# Sat_Cape_v8.net
KiCad netlist of a schematic drawn in EAGLE
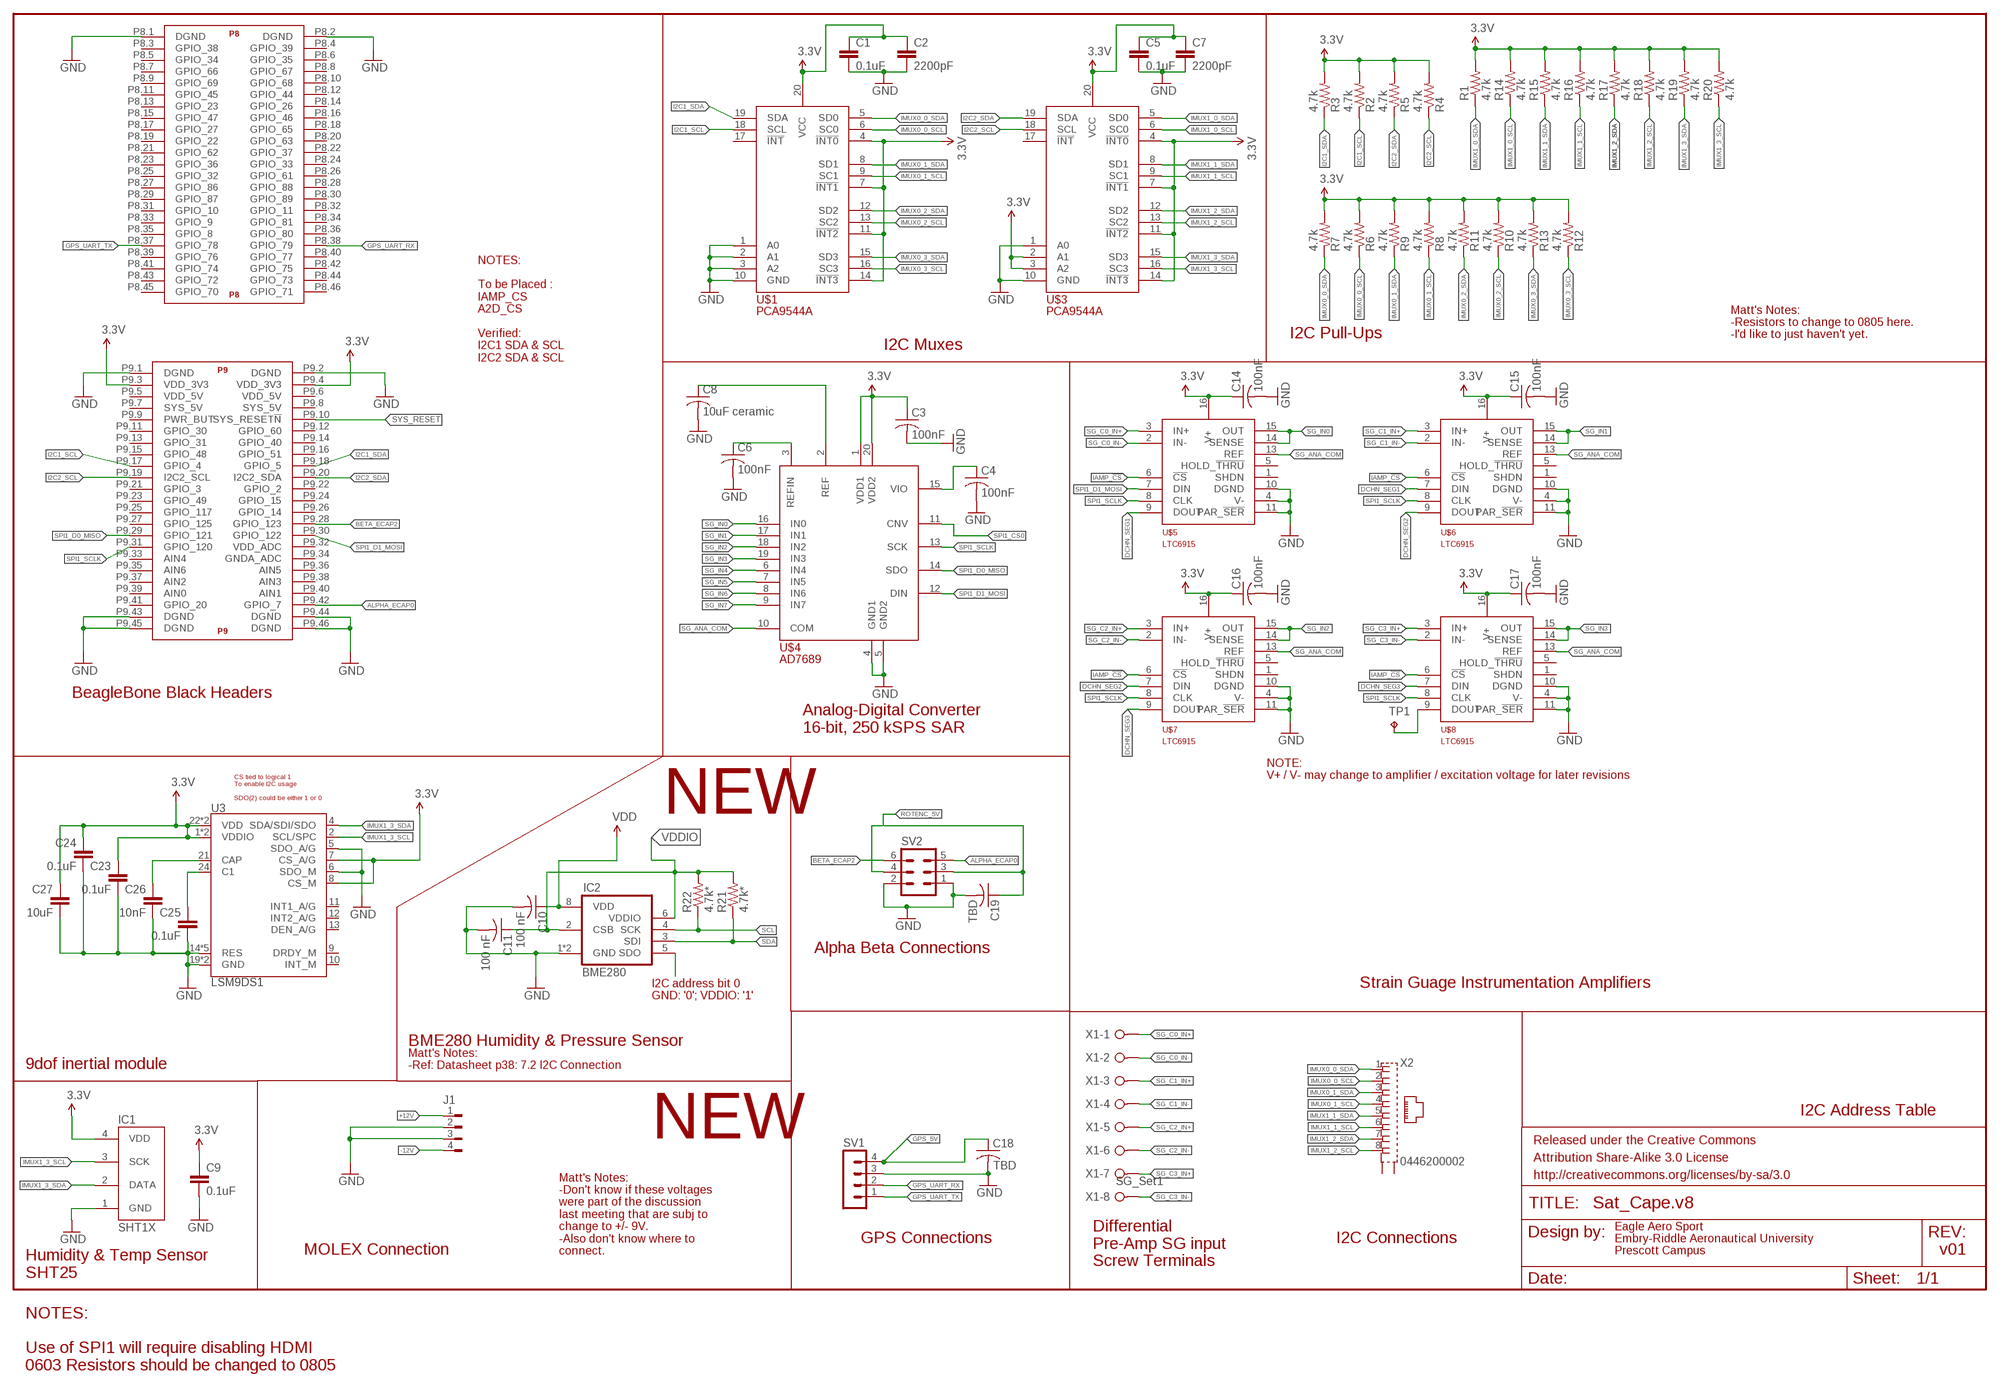
[diagram p0: schematic, sheet 1]

(export (version "E")
  (design (tool "Eeschema 10.0.6"))
  (components
    (comp (ref "C1")
      (value "0.1uF")
      (footprint "eagle-import:0603-CAP")
      (libsource (lib "eagle-import") (part "0.1UF-25V(+80/-20%)(0603)"))
    )
    (comp (ref "C2")
      (value "2200pF")
      (footprint "eagle-import:0603-CAP")
      (libsource (lib "eagle-import") (part "0.1UF-25V(+80/-20%)(0603)"))
    )
    (comp (ref "C3")
      (value "100nF")
      (footprint "eagle-import:C0805")
      (libsource (lib "eagle-import") (part "C-USC0805"))
    )
    (comp (ref "C4")
      (value "100nF")
      (footprint "eagle-import:C0805")
      (libsource (lib "eagle-import") (part "C-USC0805"))
    )
    (comp (ref "C5")
      (value "0.1uF")
      (footprint "eagle-import:0603-CAP")
      (libsource (lib "eagle-import") (part "0.1UF-25V(+80/-20%)(0603)"))
    )
    (comp (ref "C6")
      (value "100nF")
      (footprint "eagle-import:C0805")
      (libsource (lib "eagle-import") (part "C-USC0805"))
    )
    (comp (ref "C7")
      (value "2200pF")
      (footprint "eagle-import:0603-CAP")
      (libsource (lib "eagle-import") (part "0.1UF-25V(+80/-20%)(0603)"))
    )
    (comp (ref "C8")
      (value "10uF ceramic")
      (footprint "eagle-import:C0805")
      (libsource (lib "eagle-import") (part "C-USC0805"))
    )
    (comp (ref "C9")
      (value "0.1uF")
      (footprint "eagle-import:0603-CAP")
      (libsource (lib "eagle-import") (part "0.1UF-25V(+80/-20%)(0603)"))
    )
    (comp (ref "C10")
      (value "100 nF")
      (footprint "eagle-import:C0805")
      (libsource (lib "eagle-import") (part "C-USC0805"))
    )
    (comp (ref "C11")
      (value "100 nF")
      (footprint "eagle-import:C0805")
      (libsource (lib "eagle-import") (part "C-USC0805"))
    )
    (comp (ref "C14")
      (value "100nF")
      (footprint "eagle-import:C0805")
      (libsource (lib "eagle-import") (part "C-USC0805"))
    )
    (comp (ref "C15")
      (value "100nF")
      (footprint "eagle-import:C0805")
      (libsource (lib "eagle-import") (part "C-USC0805"))
    )
    (comp (ref "C16")
      (value "100nF")
      (footprint "eagle-import:C0805")
      (libsource (lib "eagle-import") (part "C-USC0805"))
    )
    (comp (ref "C17")
      (value "100nF")
      (footprint "eagle-import:C0805")
      (libsource (lib "eagle-import") (part "C-USC0805"))
    )
    (comp (ref "C18")
      (value "TBD")
      (footprint "eagle-import:C0805")
      (libsource (lib "eagle-import") (part "C-USC0805"))
    )
    (comp (ref "C19")
      (value "TBD")
      (footprint "eagle-import:C0805")
      (libsource (lib "eagle-import") (part "C-USC0805"))
    )
    (comp (ref "C23")
      (value "0.1uF")
      (footprint "eagle-import:0603-CAP")
      (libsource (lib "eagle-import") (part "0.1UF-25V(+80/-20%)(0603)"))
    )
    (comp (ref "C24")
      (value "0.1uF")
      (footprint "eagle-import:0603-CAP")
      (libsource (lib "eagle-import") (part "0.1UF-25V(+80/-20%)(0603)"))
    )
    (comp (ref "C25")
      (value "0.1uF")
      (footprint "eagle-import:0603-CAP")
      (libsource (lib "eagle-import") (part "0.1UF-25V(+80/-20%)(0603)"))
    )
    (comp (ref "C26")
      (value "10nF")
      (footprint "eagle-import:0603-CAP")
      (libsource (lib "eagle-import") (part "10NF/10000PF-50V-10%(0603)"))
    )
    (comp (ref "C27")
      (value "10uF")
      (footprint "eagle-import:0603-CAP")
      (libsource (lib "eagle-import") (part "10UF-6.3V-20%(0603)"))
    )
    (comp (ref "FRAME1")
      (value "FRAME-LEDGER")
      (footprint "eagle-import:CREATIVE_COMMONS")
      (libsource (lib "eagle-import") (part "FRAME-LEDGER"))
    )
    (comp (ref "IC1")
      (value "SHT1X")
      (footprint "eagle-import:SHT1X")
      (libsource (lib "eagle-import") (part "SHT1X"))
    )
    (comp (ref "IC2")
      (value "BME280")
      (footprint "eagle-import:BME280")
      (libsource (lib "eagle-import") (part "BME280"))
    )
    (comp (ref "J1")
      (value "FLOPPY-4350211")
      (footprint "eagle-import:350211")
      (libsource (lib "eagle-import") (part "FLOPPY-4350211"))
    )
    (comp (ref "R1")
      (value "4.7k")
      (footprint "eagle-import:R0805")
      (libsource (lib "eagle-import") (part "resistor_R-US_R0805"))
    )
    (comp (ref "R2")
      (value "4.7k")
      (footprint "eagle-import:0603-RES")
      (libsource (lib "eagle-import") (part "10KOHM1/10W1%(0603)0603"))
    )
    (comp (ref "R3")
      (value "4.7k")
      (footprint "eagle-import:0603-RES")
      (libsource (lib "eagle-import") (part "10KOHM1/10W1%(0603)0603"))
    )
    (comp (ref "R4")
      (value "4.7k")
      (footprint "eagle-import:0603-RES")
      (libsource (lib "eagle-import") (part "10KOHM1/10W1%(0603)0603"))
    )
    (comp (ref "R5")
      (value "4.7k")
      (footprint "eagle-import:0603-RES")
      (libsource (lib "eagle-import") (part "10KOHM1/10W1%(0603)0603"))
    )
    (comp (ref "R6")
      (value "4.7k")
      (footprint "eagle-import:0603-RES")
      (libsource (lib "eagle-import") (part "10KOHM1/10W1%(0603)0603"))
    )
    (comp (ref "R7")
      (value "4.7k")
      (footprint "eagle-import:0603-RES")
      (libsource (lib "eagle-import") (part "10KOHM1/10W1%(0603)0603"))
    )
    (comp (ref "R8")
      (value "4.7k")
      (footprint "eagle-import:0603-RES")
      (libsource (lib "eagle-import") (part "10KOHM1/10W1%(0603)0603"))
    )
    (comp (ref "R9")
      (value "4.7k")
      (footprint "eagle-import:0603-RES")
      (libsource (lib "eagle-import") (part "10KOHM1/10W1%(0603)0603"))
    )
    (comp (ref "R10")
      (value "4.7k")
      (footprint "eagle-import:0603-RES")
      (libsource (lib "eagle-import") (part "10KOHM1/10W1%(0603)0603"))
    )
    (comp (ref "R11")
      (value "4.7k")
      (footprint "eagle-import:0603-RES")
      (libsource (lib "eagle-import") (part "10KOHM1/10W1%(0603)0603"))
    )
    (comp (ref "R12")
      (value "4.7k")
      (footprint "eagle-import:0603-RES")
      (libsource (lib "eagle-import") (part "10KOHM1/10W1%(0603)0603"))
    )
    (comp (ref "R13")
      (value "4.7k")
      (footprint "eagle-import:0603-RES")
      (libsource (lib "eagle-import") (part "10KOHM1/10W1%(0603)0603"))
    )
    (comp (ref "R14")
      (value "4.7k")
      (footprint "eagle-import:R0805")
      (libsource (lib "eagle-import") (part "resistor_R-US_R0805"))
    )
    (comp (ref "R15")
      (value "4.7k")
      (footprint "eagle-import:R0805")
      (libsource (lib "eagle-import") (part "resistor_R-US_R0805"))
    )
    (comp (ref "R16")
      (value "4.7k")
      (footprint "eagle-import:R0805")
      (libsource (lib "eagle-import") (part "resistor_R-US_R0805"))
    )
    (comp (ref "R17")
      (value "4.7k")
      (footprint "eagle-import:R0805")
      (libsource (lib "eagle-import") (part "resistor_R-US_R0805"))
    )
    (comp (ref "R18")
      (value "4.7k")
      (footprint "eagle-import:R0805")
      (libsource (lib "eagle-import") (part "resistor_R-US_R0805"))
    )
    (comp (ref "R19")
      (value "4.7k")
      (footprint "eagle-import:R0805")
      (libsource (lib "eagle-import") (part "resistor_R-US_R0805"))
    )
    (comp (ref "R20")
      (value "4.7k")
      (footprint "eagle-import:R0805")
      (libsource (lib "eagle-import") (part "resistor_R-US_R0805"))
    )
    (comp (ref "R21")
      (value "4.7k*")
      (footprint "eagle-import:R0805")
      (libsource (lib "eagle-import") (part "R-US_R0805"))
    )
    (comp (ref "R22")
      (value "4.7k*")
      (footprint "eagle-import:R0805")
      (libsource (lib "eagle-import") (part "R-US_R0805"))
    )
    (comp (ref "SV1")
      (value "MA04-1")
      (footprint "eagle-import:MA04-1")
      (libsource (lib "eagle-import") (part "MA04-1"))
    )
    (comp (ref "SV2")
      (value "MA03-2")
      (footprint "eagle-import:MA03-2")
      (libsource (lib "eagle-import") (part "MA03-2"))
    )
    (comp (ref "TP1")
      (value "TPTP08R")
      (footprint "eagle-import:TP08R")
      (libsource (lib "eagle-import") (part "TPTP08R"))
    )
    (comp (ref "U$1")
      (value "PCA9544A")
      (footprint "eagle-import:TSSOP20")
      (libsource (lib "eagle-import") (part "PCA9544A"))
    )
    (comp (ref "U$2")
      (value "BEAGLE_BONE_BLACK_CAPE")
      (footprint "eagle-import:BEAGLE_BONE_BLACK_CAPE")
      (libsource (lib "eagle-import") (part "BEAGLE_BONE_BLACK_CAPE"))
    )
    (comp (ref "U$3")
      (value "PCA9544A")
      (footprint "eagle-import:TSSOP20")
      (libsource (lib "eagle-import") (part "PCA9544A"))
    )
    (comp (ref "U$4")
      (value "AD7689")
      (footprint "eagle-import:QFN20")
      (libsource (lib "eagle-import") (part "AD7689"))
    )
    (comp (ref "U$5")
      (value "LTC6915")
      (footprint "eagle-import:SSOP16")
      (libsource (lib "eagle-import") (part "LTC6915"))
    )
    (comp (ref "U$6")
      (value "LTC6915")
      (footprint "eagle-import:SSOP16")
      (libsource (lib "eagle-import") (part "LTC6915"))
    )
    (comp (ref "U$7")
      (value "LTC6915")
      (footprint "eagle-import:SSOP16")
      (libsource (lib "eagle-import") (part "LTC6915"))
    )
    (comp (ref "U$8")
      (value "LTC6915")
      (footprint "eagle-import:SSOP16")
      (libsource (lib "eagle-import") (part "LTC6915"))
    )
    (comp (ref "U3")
      (value "LSM9DS1")
      (footprint "eagle-import:LGA24-8X4")
      (libsource (lib "eagle-import") (part "LSM9DS1"))
    )
    (comp (ref "X1")
      (value "SG_Set1")
      (footprint "eagle-import:W237-8P")
      (libsource (lib "eagle-import") (part "W237-08P"))
    )
    (comp (ref "X2")
      (value "0446200002")
      (footprint "eagle-import:0446200002")
      (fields (field (name "MF") "MOLEX"))
      (libsource (lib "eagle-import") (part "0446200002"))
    )
  )
  (nets
    (net (code "1") (name "+12V") (class "Default")
      (node (ref "J1") (pin "1") (pinfunction "1_1") (pintype "passive"))
    )
    (net (code "2") (name "-12V") (class "Default")
      (node (ref "J1") (pin "4") (pinfunction "4_4") (pintype "passive"))
    )
    (net (code "3") (name "/IAMP_~{CS}") (class "Default")
      (node (ref "U$5") (pin "6") (pinfunction "~{CS}_6") (pintype "bidirectional"))
      (node (ref "U$6") (pin "6") (pinfunction "~{CS}_6") (pintype "bidirectional"))
      (node (ref "U$7") (pin "6") (pinfunction "~{CS}_6") (pintype "bidirectional"))
      (node (ref "U$8") (pin "6") (pinfunction "~{CS}_6") (pintype "bidirectional"))
    )
    (net (code "4") (name "3.3V") (class "Default")
      (node (ref "C1") (pin "1") (pinfunction "1_1") (pintype "passive"))
      (node (ref "C14") (pin "1") (pinfunction "1_1") (pintype "passive"))
      (node (ref "C15") (pin "1") (pinfunction "1_1") (pintype "passive"))
      (node (ref "C16") (pin "1") (pinfunction "1_1") (pintype "passive"))
      (node (ref "C17") (pin "1") (pinfunction "1_1") (pintype "passive"))
      (node (ref "C2") (pin "1") (pinfunction "1_1") (pintype "passive"))
      (node (ref "C23") (pin "1") (pinfunction "1_1") (pintype "passive"))
      (node (ref "C24") (pin "1") (pinfunction "1_1") (pintype "passive"))
      (node (ref "C27") (pin "1") (pinfunction "1_1") (pintype "passive"))
      (node (ref "C3") (pin "1") (pinfunction "1_1") (pintype "passive"))
      (node (ref "C5") (pin "1") (pinfunction "1_1") (pintype "passive"))
      (node (ref "C7") (pin "1") (pinfunction "1_1") (pintype "passive"))
      (node (ref "C9") (pin "1") (pinfunction "1_1") (pintype "passive"))
      (node (ref "IC1") (pin "4") (pinfunction "VDD_4") (pintype "power_in"))
      (node (ref "R1") (pin "2") (pinfunction "2_2") (pintype "passive"))
      (node (ref "R10") (pin "2") (pinfunction "2_2") (pintype "passive"))
      (node (ref "R11") (pin "2") (pinfunction "2_2") (pintype "passive"))
      (node (ref "R12") (pin "2") (pinfunction "2_2") (pintype "passive"))
      (node (ref "R13") (pin "2") (pinfunction "2_2") (pintype "passive"))
      (node (ref "R14") (pin "2") (pinfunction "2_2") (pintype "passive"))
      (node (ref "R15") (pin "2") (pinfunction "2_2") (pintype "passive"))
      (node (ref "R16") (pin "2") (pinfunction "2_2") (pintype "passive"))
      (node (ref "R17") (pin "2") (pinfunction "2_2") (pintype "passive"))
      (node (ref "R18") (pin "2") (pinfunction "2_2") (pintype "passive"))
      (node (ref "R19") (pin "2") (pinfunction "2_2") (pintype "passive"))
      (node (ref "R2") (pin "2") (pinfunction "2_2") (pintype "passive"))
      (node (ref "R20") (pin "2") (pinfunction "2_2") (pintype "passive"))
      (node (ref "R3") (pin "2") (pinfunction "2_2") (pintype "passive"))
      (node (ref "R4") (pin "2") (pinfunction "2_2") (pintype "passive"))
      (node (ref "R5") (pin "2") (pinfunction "2_2") (pintype "passive"))
      (node (ref "R6") (pin "2") (pinfunction "2_2") (pintype "passive"))
      (node (ref "R7") (pin "2") (pinfunction "2_2") (pintype "passive"))
      (node (ref "R8") (pin "2") (pinfunction "2_2") (pintype "passive"))
      (node (ref "R9") (pin "2") (pinfunction "2_2") (pintype "passive"))
      (node (ref "U$1") (pin "11") (pinfunction "~{INT2}_11") (pintype "input"))
      (node (ref "U$1") (pin "14") (pinfunction "~{INT3}_14") (pintype "input"))
      (node (ref "U$1") (pin "20") (pinfunction "VCC_20") (pintype "power_in"))
      (node (ref "U$1") (pin "4") (pinfunction "~{INT0}_4") (pintype "input"))
      (node (ref "U$1") (pin "7") (pinfunction "~{INT1}_7") (pintype "input"))
      (node (ref "U$2") (pin "P9.3") (pinfunction "VDD_3V3_P9.3") (pintype "bidirectional"))
      (node (ref "U$2") (pin "P9.4") (pinfunction "VDD_3V3_P9.4") (pintype "bidirectional"))
      (node (ref "U$3") (pin "11") (pinfunction "~{INT2}_11") (pintype "input"))
      (node (ref "U$3") (pin "14") (pinfunction "~{INT3}_14") (pintype "input"))
      (node (ref "U$3") (pin "2") (pinfunction "A1_2") (pintype "input"))
      (node (ref "U$3") (pin "20") (pinfunction "VCC_20") (pintype "power_in"))
      (node (ref "U$3") (pin "3") (pinfunction "A2_3") (pintype "input"))
      (node (ref "U$3") (pin "4") (pinfunction "~{INT0}_4") (pintype "input"))
      (node (ref "U$3") (pin "7") (pinfunction "~{INT1}_7") (pintype "input"))
      (node (ref "U$4") (pin "1") (pinfunction "VDD1_1") (pintype "bidirectional"))
      (node (ref "U$4") (pin "20") (pinfunction "VDD2_20") (pintype "bidirectional"))
      (node (ref "U$5") (pin "16") (pinfunction "V+_16") (pintype "bidirectional"))
      (node (ref "U$6") (pin "16") (pinfunction "V+_16") (pintype "bidirectional"))
      (node (ref "U$7") (pin "16") (pinfunction "V+_16") (pintype "bidirectional"))
      (node (ref "U$8") (pin "16") (pinfunction "V+_16") (pintype "bidirectional"))
      (node (ref "U3") (pin "1") (pinfunction "VDDIO_1") (pintype "bidirectional"))
      (node (ref "U3") (pin "22") (pinfunction "VDD_22") (pintype "bidirectional"))
      (node (ref "U3") (pin "23") (pinfunction "VDD_23") (pintype "bidirectional"))
      (node (ref "U3") (pin "3") (pinfunction "VDDIO_3") (pintype "bidirectional"))
      (node (ref "U3") (pin "7") (pinfunction "CS_A/G_7") (pintype "bidirectional"))
      (node (ref "U3") (pin "8") (pinfunction "CS_M_8") (pintype "bidirectional"))
    )
    (net (code "5") (name "ALPHA_ECAP0") (class "Default")
      (node (ref "SV2") (pin "5") (pinfunction "5_5") (pintype "passive"))
      (node (ref "U$2") (pin "P9.42") (pinfunction "GPIO_7_P9.42") (pintype "bidirectional"))
    )
    (net (code "6") (name "BETA_ECAP2") (class "Default")
      (node (ref "SV2") (pin "6") (pinfunction "6_6") (pintype "passive"))
      (node (ref "U$2") (pin "P9.28") (pinfunction "GPIO_123_P9.28") (pintype "bidirectional"))
    )
    (net (code "7") (name "DCHN_SEG1") (class "Default")
      (node (ref "U$5") (pin "9") (pinfunction "DOUT_9") (pintype "bidirectional"))
      (node (ref "U$6") (pin "7") (pinfunction "DIN_7") (pintype "bidirectional"))
    )
    (net (code "8") (name "DCHN_SEG2") (class "Default")
      (node (ref "U$6") (pin "9") (pinfunction "DOUT_9") (pintype "bidirectional"))
      (node (ref "U$7") (pin "7") (pinfunction "DIN_7") (pintype "bidirectional"))
    )
    (net (code "9") (name "DCHN_SEG3") (class "Default")
      (node (ref "U$7") (pin "9") (pinfunction "DOUT_9") (pintype "bidirectional"))
      (node (ref "U$8") (pin "7") (pinfunction "DIN_7") (pintype "bidirectional"))
    )
    (net (code "10") (name "GND") (class "Default")
      (node (ref "C1") (pin "2") (pinfunction "2_2") (pintype "passive"))
      (node (ref "C10") (pin "2") (pinfunction "2_2") (pintype "passive"))
      (node (ref "C11") (pin "2") (pinfunction "2_2") (pintype "passive"))
      (node (ref "C14") (pin "2") (pinfunction "2_2") (pintype "passive"))
      (node (ref "C15") (pin "2") (pinfunction "2_2") (pintype "passive"))
      (node (ref "C16") (pin "2") (pinfunction "2_2") (pintype "passive"))
      (node (ref "C17") (pin "2") (pinfunction "2_2") (pintype "passive"))
      (node (ref "C18") (pin "2") (pinfunction "2_2") (pintype "passive"))
      (node (ref "C19") (pin "2") (pinfunction "2_2") (pintype "passive"))
      (node (ref "C2") (pin "2") (pinfunction "2_2") (pintype "passive"))
      (node (ref "C23") (pin "2") (pinfunction "2_2") (pintype "passive"))
      (node (ref "C24") (pin "2") (pinfunction "2_2") (pintype "passive"))
      (node (ref "C25") (pin "2") (pinfunction "2_2") (pintype "passive"))
      (node (ref "C26") (pin "2") (pinfunction "2_2") (pintype "passive"))
      (node (ref "C27") (pin "2") (pinfunction "2_2") (pintype "passive"))
      (node (ref "C3") (pin "2") (pinfunction "2_2") (pintype "passive"))
      (node (ref "C4") (pin "2") (pinfunction "2_2") (pintype "passive"))
      (node (ref "C5") (pin "2") (pinfunction "2_2") (pintype "passive"))
      (node (ref "C6") (pin "2") (pinfunction "2_2") (pintype "passive"))
      (node (ref "C7") (pin "2") (pinfunction "2_2") (pintype "passive"))
      (node (ref "C8") (pin "2") (pinfunction "2_2") (pintype "passive"))
      (node (ref "C9") (pin "2") (pinfunction "2_2") (pintype "passive"))
      (node (ref "IC1") (pin "1") (pinfunction "GND_1") (pintype "power_in"))
      (node (ref "IC2") (pin "1") (pinfunction "GND_1") (pintype "power_in"))
      (node (ref "IC2") (pin "7") (pinfunction "GND_7") (pintype "power_in"))
      (node (ref "J1") (pin "2") (pinfunction "2_2") (pintype "passive"))
      (node (ref "J1") (pin "3") (pinfunction "3_3") (pintype "passive"))
      (node (ref "SV1") (pin "3") (pinfunction "3_3") (pintype "passive"))
      (node (ref "SV2") (pin "1") (pinfunction "1_1") (pintype "passive"))
      (node (ref "SV2") (pin "2") (pinfunction "2_2") (pintype "passive"))
      (node (ref "U$1") (pin "1") (pinfunction "A0_1") (pintype "input"))
      (node (ref "U$1") (pin "10") (pinfunction "GND_10") (pintype "power_in"))
      (node (ref "U$1") (pin "2") (pinfunction "A1_2") (pintype "input"))
      (node (ref "U$1") (pin "3") (pinfunction "A2_3") (pintype "input"))
      (node (ref "U$2") (pin "P8.1") (pinfunction "DGND_P8.1") (pintype "bidirectional"))
      (node (ref "U$2") (pin "P8.2") (pinfunction "DGND_P8.2") (pintype "bidirectional"))
      (node (ref "U$2") (pin "P9.1") (pinfunction "DGND_P9.1") (pintype "bidirectional"))
      (node (ref "U$2") (pin "P9.2") (pinfunction "DGND_P9.2") (pintype "bidirectional"))
      (node (ref "U$2") (pin "P9.43") (pinfunction "DGND_P9.43") (pintype "bidirectional"))
      (node (ref "U$2") (pin "P9.44") (pinfunction "DGND_P9.44") (pintype "bidirectional"))
      (node (ref "U$2") (pin "P9.45") (pinfunction "DGND_P9.45") (pintype "bidirectional"))
      (node (ref "U$2") (pin "P9.46") (pinfunction "DGND_P9.46") (pintype "bidirectional"))
      (node (ref "U$3") (pin "1") (pinfunction "A0_1") (pintype "input"))
      (node (ref "U$3") (pin "10") (pinfunction "GND_10") (pintype "power_in"))
      (node (ref "U$4") (pin "4") (pinfunction "GND1_4") (pintype "bidirectional"))
      (node (ref "U$4") (pin "5") (pinfunction "GND2_5") (pintype "bidirectional"))
      (node (ref "U$5") (pin "10") (pinfunction "DGND_10") (pintype "bidirectional"))
      (node (ref "U$5") (pin "11") (pinfunction "PAR_~{SER}_11") (pintype "bidirectional"))
      (node (ref "U$5") (pin "4") (pinfunction "V-_4") (pintype "bidirectional"))
      (node (ref "U$6") (pin "10") (pinfunction "DGND_10") (pintype "bidirectional"))
      (node (ref "U$6") (pin "11") (pinfunction "PAR_~{SER}_11") (pintype "bidirectional"))
      (node (ref "U$6") (pin "4") (pinfunction "V-_4") (pintype "bidirectional"))
      (node (ref "U$7") (pin "10") (pinfunction "DGND_10") (pintype "bidirectional"))
      (node (ref "U$7") (pin "11") (pinfunction "PAR_~{SER}_11") (pintype "bidirectional"))
      (node (ref "U$7") (pin "4") (pinfunction "V-_4") (pintype "bidirectional"))
      (node (ref "U$8") (pin "10") (pinfunction "DGND_10") (pintype "bidirectional"))
      (node (ref "U$8") (pin "11") (pinfunction "PAR_~{SER}_11") (pintype "bidirectional"))
      (node (ref "U$8") (pin "4") (pinfunction "V-_4") (pintype "bidirectional"))
      (node (ref "U3") (pin "14") (pinfunction "RES_14") (pintype "bidirectional"))
      (node (ref "U3") (pin "15") (pinfunction "RES_15") (pintype "bidirectional"))
      (node (ref "U3") (pin "16") (pinfunction "RES_16") (pintype "bidirectional"))
      (node (ref "U3") (pin "17") (pinfunction "RES_17") (pintype "bidirectional"))
      (node (ref "U3") (pin "18") (pinfunction "RES_18") (pintype "bidirectional"))
      (node (ref "U3") (pin "19") (pinfunction "GND_19") (pintype "bidirectional"))
      (node (ref "U3") (pin "20") (pinfunction "GND_20") (pintype "bidirectional"))
      (node (ref "U3") (pin "5") (pinfunction "SDO_A/G_5") (pintype "bidirectional"))
      (node (ref "U3") (pin "6") (pinfunction "SDO_M_6") (pintype "bidirectional"))
    )
    (net (code "11") (name "GPS_5V") (class "Default")
      (node (ref "C18") (pin "1") (pinfunction "1_1") (pintype "passive"))
      (node (ref "SV1") (pin "4") (pinfunction "4_4") (pintype "passive"))
    )
    (net (code "12") (name "GPS_UART_RX") (class "Default")
      (node (ref "SV1") (pin "2") (pinfunction "2_2") (pintype "passive"))
      (node (ref "U$2") (pin "P8.38") (pinfunction "GPIO_79_P8.38") (pintype "bidirectional"))
    )
    (net (code "13") (name "GPS_UART_TX") (class "Default")
      (node (ref "SV1") (pin "1") (pinfunction "1_1") (pintype "passive"))
      (node (ref "U$2") (pin "P8.37") (pinfunction "GPIO_78_P8.37") (pintype "bidirectional"))
    )
    (net (code "14") (name "I2C1_SCL") (class "Default")
      (node (ref "R2") (pin "1") (pinfunction "1_1") (pintype "passive"))
      (node (ref "U$1") (pin "18") (pinfunction "SCL_18") (pintype "input"))
      (node (ref "U$2") (pin "P9.17") (pinfunction "GPIO_4_P9.17") (pintype "bidirectional"))
    )
    (net (code "15") (name "I2C1_SDA") (class "Default")
      (node (ref "R3") (pin "1") (pinfunction "1_1") (pintype "passive"))
      (node (ref "U$1") (pin "19") (pinfunction "SDA_19") (pintype "bidirectional"))
      (node (ref "U$2") (pin "P9.18") (pinfunction "GPIO_5_P9.18") (pintype "bidirectional"))
    )
    (net (code "16") (name "I2C2_SCL") (class "Default")
      (node (ref "R4") (pin "1") (pinfunction "1_1") (pintype "passive"))
      (node (ref "U$2") (pin "P9.19") (pinfunction "I2C2_SCL_P9.19") (pintype "bidirectional"))
      (node (ref "U$3") (pin "18") (pinfunction "SCL_18") (pintype "input"))
    )
    (net (code "17") (name "I2C2_SDA") (class "Default")
      (node (ref "R5") (pin "1") (pinfunction "1_1") (pintype "passive"))
      (node (ref "U$2") (pin "P9.20") (pinfunction "I2C2_SDA_P9.20") (pintype "bidirectional"))
      (node (ref "U$3") (pin "19") (pinfunction "SDA_19") (pintype "bidirectional"))
    )
    (net (code "18") (name "IMUX0_0_SCL") (class "Default")
      (node (ref "R6") (pin "1") (pinfunction "1_1") (pintype "passive"))
      (node (ref "U$1") (pin "6") (pinfunction "SC0_6") (pintype "output"))
      (node (ref "X2") (pin "2") (pinfunction "2_2") (pintype "passive"))
    )
    (net (code "19") (name "IMUX0_0_SDA") (class "Default")
      (node (ref "R7") (pin "1") (pinfunction "1_1") (pintype "passive"))
      (node (ref "U$1") (pin "5") (pinfunction "SD0_5") (pintype "bidirectional"))
      (node (ref "X2") (pin "1") (pinfunction "1_1") (pintype "passive"))
    )
    (net (code "20") (name "IMUX0_1_SCL") (class "Default")
      (node (ref "R8") (pin "1") (pinfunction "1_1") (pintype "passive"))
      (node (ref "U$1") (pin "9") (pinfunction "SC1_9") (pintype "output"))
      (node (ref "X2") (pin "4") (pinfunction "4_4") (pintype "passive"))
    )
    (net (code "21") (name "IMUX0_1_SDA") (class "Default")
      (node (ref "R9") (pin "1") (pinfunction "1_1") (pintype "passive"))
      (node (ref "U$1") (pin "8") (pinfunction "SD1_8") (pintype "bidirectional"))
      (node (ref "X2") (pin "3") (pinfunction "3_3") (pintype "passive"))
    )
    (net (code "22") (name "IMUX0_2_SCL") (class "Default")
      (node (ref "R10") (pin "1") (pinfunction "1_1") (pintype "passive"))
      (node (ref "U$1") (pin "13") (pinfunction "SC2_13") (pintype "output"))
    )
    (net (code "23") (name "IMUX0_2_SDA") (class "Default")
      (node (ref "R11") (pin "1") (pinfunction "1_1") (pintype "passive"))
      (node (ref "U$1") (pin "12") (pinfunction "SD2_12") (pintype "bidirectional"))
    )
    (net (code "24") (name "IMUX0_3_SCL") (class "Default")
      (node (ref "R12") (pin "1") (pinfunction "1_1") (pintype "passive"))
      (node (ref "U$1") (pin "16") (pinfunction "SC3_16") (pintype "output"))
    )
    (net (code "25") (name "IMUX0_3_SDA") (class "Default")
      (node (ref "R13") (pin "1") (pinfunction "1_1") (pintype "passive"))
      (node (ref "U$1") (pin "15") (pinfunction "SD3_15") (pintype "bidirectional"))
    )
    (net (code "26") (name "IMUX1_0_SCL") (class "Default")
      (node (ref "R14") (pin "1") (pinfunction "1_1") (pintype "passive"))
      (node (ref "U$3") (pin "6") (pinfunction "SC0_6") (pintype "output"))
    )
    (net (code "27") (name "IMUX1_0_SDA") (class "Default")
      (node (ref "R1") (pin "1") (pinfunction "1_1") (pintype "passive"))
      (node (ref "U$3") (pin "5") (pinfunction "SD0_5") (pintype "bidirectional"))
    )
    (net (code "28") (name "IMUX1_1_SCL") (class "Default")
      (node (ref "R16") (pin "1") (pinfunction "1_1") (pintype "passive"))
      (node (ref "U$3") (pin "9") (pinfunction "SC1_9") (pintype "output"))
      (node (ref "X2") (pin "6") (pinfunction "6_6") (pintype "passive"))
    )
    (net (code "29") (name "IMUX1_1_SDA") (class "Default")
      (node (ref "R15") (pin "1") (pinfunction "1_1") (pintype "passive"))
      (node (ref "U$3") (pin "8") (pinfunction "SD1_8") (pintype "bidirectional"))
      (node (ref "X2") (pin "5") (pinfunction "5_5") (pintype "passive"))
    )
    (net (code "30") (name "IMUX1_2_SCL") (class "Default")
      (node (ref "R18") (pin "1") (pinfunction "1_1") (pintype "passive"))
      (node (ref "U$3") (pin "13") (pinfunction "SC2_13") (pintype "output"))
      (node (ref "X2") (pin "8") (pinfunction "8_8") (pintype "passive"))
    )
    (net (code "31") (name "IMUX1_2_SDA") (class "Default")
      (node (ref "R17") (pin "1") (pinfunction "1_1") (pintype "passive"))
      (node (ref "U$3") (pin "12") (pinfunction "SD2_12") (pintype "bidirectional"))
      (node (ref "X2") (pin "7") (pinfunction "7_7") (pintype "passive"))
    )
    (net (code "32") (name "IMUX1_3_SCL") (class "Default")
      (node (ref "IC1") (pin "3") (pinfunction "SCK_3") (pintype "input"))
      (node (ref "R20") (pin "1") (pinfunction "1_1") (pintype "passive"))
      (node (ref "U$3") (pin "16") (pinfunction "SC3_16") (pintype "output"))
      (node (ref "U3") (pin "2") (pinfunction "SCL/SPC_2") (pintype "bidirectional"))
    )
    (net (code "33") (name "IMUX1_3_SDA") (class "Default")
      (node (ref "IC1") (pin "2") (pinfunction "DATA_2") (pintype "open_collector"))
      (node (ref "R19") (pin "1") (pinfunction "1_1") (pintype "passive"))
      (node (ref "U$3") (pin "15") (pinfunction "SD3_15") (pintype "bidirectional"))
      (node (ref "U3") (pin "4") (pinfunction "SDA/SDI/SDO_4") (pintype "bidirectional"))
    )
    (net (code "34") (name "Net-(U$4-REF)") (class "Default")
      (node (ref "C8") (pin "1") (pinfunction "1_1") (pintype "passive"))
      (node (ref "U$4") (pin "2") (pinfunction "REF_2") (pintype "bidirectional"))
    )
    (net (code "35") (name "Net-(U$4-REFIN)") (class "Default")
      (node (ref "C6") (pin "1") (pinfunction "1_1") (pintype "passive"))
      (node (ref "U$4") (pin "3") (pinfunction "REFIN_3") (pintype "bidirectional"))
    )
    (net (code "36") (name "Net-(U$4-VIO)") (class "Default")
      (node (ref "C4") (pin "1") (pinfunction "1_1") (pintype "passive"))
      (node (ref "U$4") (pin "15") (pinfunction "VIO_15") (pintype "bidirectional"))
    )
    (net (code "37") (name "Net-(U$8-DOUT)") (class "Default")
      (node (ref "TP1") (pin "TP") (pinfunction "TP_TP") (pintype "input"))
      (node (ref "U$8") (pin "9") (pinfunction "DOUT_9") (pintype "bidirectional"))
    )
    (net (code "38") (name "Net-(U3-C1)") (class "Default")
      (node (ref "C25") (pin "1") (pinfunction "1_1") (pintype "passive"))
      (node (ref "U3") (pin "24") (pinfunction "C1_24") (pintype "bidirectional"))
    )
    (net (code "39") (name "Net-(U3-CAP)") (class "Default")
      (node (ref "C26") (pin "1") (pinfunction "1_1") (pintype "passive"))
      (node (ref "U3") (pin "21") (pinfunction "CAP_21") (pintype "bidirectional"))
    )
    (net (code "40") (name "ROTENC_5V") (class "Default")
      (node (ref "C19") (pin "1") (pinfunction "1_1") (pintype "passive"))
      (node (ref "SV2") (pin "3") (pinfunction "3_3") (pintype "passive"))
      (node (ref "SV2") (pin "4") (pinfunction "4_4") (pintype "passive"))
    )
    (net (code "41") (name "SCL") (class "Default")
      (node (ref "IC2") (pin "4") (pinfunction "SCK_4") (pintype "bidirectional"))
      (node (ref "R22") (pin "1") (pinfunction "1_1") (pintype "passive"))
    )
    (net (code "42") (name "SDA") (class "Default")
      (node (ref "IC2") (pin "3") (pinfunction "SDI_3") (pintype "bidirectional"))
      (node (ref "R21") (pin "1") (pinfunction "1_1") (pintype "passive"))
    )
    (net (code "43") (name "SG_ANA_COM") (class "Default")
      (node (ref "U$4") (pin "10") (pinfunction "COM_10") (pintype "bidirectional"))
      (node (ref "U$5") (pin "13") (pinfunction "REF_13") (pintype "bidirectional"))
      (node (ref "U$6") (pin "13") (pinfunction "REF_13") (pintype "bidirectional"))
      (node (ref "U$7") (pin "13") (pinfunction "REF_13") (pintype "bidirectional"))
      (node (ref "U$8") (pin "13") (pinfunction "REF_13") (pintype "bidirectional"))
    )
    (net (code "44") (name "SG_C0_IN+") (class "Default")
      (node (ref "U$5") (pin "3") (pinfunction "IN+_3") (pintype "bidirectional"))
      (node (ref "X1") (pin "1") (pinfunction "KL_1") (pintype "passive"))
    )
    (net (code "45") (name "SG_C0_IN-") (class "Default")
      (node (ref "U$5") (pin "2") (pinfunction "IN-_2") (pintype "bidirectional"))
      (node (ref "X1") (pin "2") (pinfunction "KL_2") (pintype "passive"))
    )
    (net (code "46") (name "SG_C1_IN+") (class "Default")
      (node (ref "U$6") (pin "3") (pinfunction "IN+_3") (pintype "bidirectional"))
      (node (ref "X1") (pin "3") (pinfunction "KL_3") (pintype "passive"))
    )
    (net (code "47") (name "SG_C1_IN-") (class "Default")
      (node (ref "U$6") (pin "2") (pinfunction "IN-_2") (pintype "bidirectional"))
      (node (ref "X1") (pin "4") (pinfunction "KL_4") (pintype "passive"))
    )
    (net (code "48") (name "SG_C2_IN+") (class "Default")
      (node (ref "U$7") (pin "3") (pinfunction "IN+_3") (pintype "bidirectional"))
      (node (ref "X1") (pin "5") (pinfunction "KL_5") (pintype "passive"))
    )
    (net (code "49") (name "SG_C2_IN-") (class "Default")
      (node (ref "U$7") (pin "2") (pinfunction "IN-_2") (pintype "bidirectional"))
      (node (ref "X1") (pin "6") (pinfunction "KL_6") (pintype "passive"))
    )
    (net (code "50") (name "SG_C3_IN+") (class "Default")
      (node (ref "U$8") (pin "3") (pinfunction "IN+_3") (pintype "bidirectional"))
      (node (ref "X1") (pin "7") (pinfunction "KL_7") (pintype "passive"))
    )
    (net (code "51") (name "SG_C3_IN-") (class "Default")
      (node (ref "U$8") (pin "2") (pinfunction "IN-_2") (pintype "bidirectional"))
      (node (ref "X1") (pin "8") (pinfunction "KL_8") (pintype "passive"))
    )
    (net (code "52") (name "SG_IN0") (class "Default")
      (node (ref "U$4") (pin "16") (pinfunction "IN0_16") (pintype "bidirectional"))
      (node (ref "U$5") (pin "14") (pinfunction "SENSE_14") (pintype "bidirectional"))
      (node (ref "U$5") (pin "15") (pinfunction "OUT_15") (pintype "bidirectional"))
    )
    (net (code "53") (name "SG_IN1") (class "Default")
      (node (ref "U$4") (pin "17") (pinfunction "IN1_17") (pintype "bidirectional"))
      (node (ref "U$6") (pin "14") (pinfunction "SENSE_14") (pintype "bidirectional"))
      (node (ref "U$6") (pin "15") (pinfunction "OUT_15") (pintype "bidirectional"))
    )
    (net (code "54") (name "SG_IN2") (class "Default")
      (node (ref "U$4") (pin "18") (pinfunction "IN2_18") (pintype "bidirectional"))
      (node (ref "U$7") (pin "14") (pinfunction "SENSE_14") (pintype "bidirectional"))
      (node (ref "U$7") (pin "15") (pinfunction "OUT_15") (pintype "bidirectional"))
    )
    (net (code "55") (name "SG_IN3") (class "Default")
      (node (ref "U$4") (pin "19") (pinfunction "IN3_19") (pintype "bidirectional"))
      (node (ref "U$8") (pin "14") (pinfunction "SENSE_14") (pintype "bidirectional"))
      (node (ref "U$8") (pin "15") (pinfunction "OUT_15") (pintype "bidirectional"))
    )
    (net (code "56") (name "SG_IN4") (class "Default")
      (node (ref "U$4") (pin "6") (pinfunction "IN4_6") (pintype "bidirectional"))
    )
    (net (code "57") (name "SG_IN5") (class "Default")
      (node (ref "U$4") (pin "7") (pinfunction "IN5_7") (pintype "bidirectional"))
    )
    (net (code "58") (name "SG_IN6") (class "Default")
      (node (ref "U$4") (pin "8") (pinfunction "IN6_8") (pintype "bidirectional"))
    )
    (net (code "59") (name "SG_IN7") (class "Default")
      (node (ref "U$4") (pin "9") (pinfunction "IN7_9") (pintype "bidirectional"))
    )
    (net (code "60") (name "SPI1_CS0") (class "Default")
      (node (ref "U$4") (pin "11") (pinfunction "CNV_11") (pintype "bidirectional"))
    )
    (net (code "61") (name "SPI1_D0_MISO") (class "Default")
      (node (ref "U$2") (pin "P9.29") (pinfunction "GPIO_121_P9.29") (pintype "bidirectional"))
      (node (ref "U$4") (pin "14") (pinfunction "SDO_14") (pintype "bidirectional"))
    )
    (net (code "62") (name "SPI1_D1_MOSI") (class "Default")
      (node (ref "U$2") (pin "P9.30") (pinfunction "GPIO_122_P9.30") (pintype "bidirectional"))
      (node (ref "U$4") (pin "12") (pinfunction "DIN_12") (pintype "bidirectional"))
      (node (ref "U$5") (pin "7") (pinfunction "DIN_7") (pintype "bidirectional"))
    )
    (net (code "63") (name "SPI1_SCLK") (class "Default")
      (node (ref "U$2") (pin "P9.31") (pinfunction "GPIO_120_P9.31") (pintype "bidirectional"))
      (node (ref "U$4") (pin "13") (pinfunction "SCK_13") (pintype "bidirectional"))
      (node (ref "U$5") (pin "8") (pinfunction "CLK_8") (pintype "bidirectional"))
      (node (ref "U$6") (pin "8") (pinfunction "CLK_8") (pintype "bidirectional"))
      (node (ref "U$7") (pin "8") (pinfunction "CLK_8") (pintype "bidirectional"))
      (node (ref "U$8") (pin "8") (pinfunction "CLK_8") (pintype "bidirectional"))
    )
    (net (code "64") (name "SYS_RESET") (class "Default")
      (node (ref "U$2") (pin "P9.10") (pinfunction "SYS_RESET~{N}_P9.10") (pintype "bidirectional"))
    )
    (net (code "65") (name "VDD") (class "Default")
      (node (ref "C10") (pin "1") (pinfunction "1_1") (pintype "passive"))
      (node (ref "IC2") (pin "8") (pinfunction "VDD_8") (pintype "power_in"))
    )
    (net (code "66") (name "VDDIO") (class "Default")
      (node (ref "C11") (pin "1") (pinfunction "1_1") (pintype "passive"))
      (node (ref "IC2") (pin "2") (pinfunction "CSB_2") (pintype "input"))
      (node (ref "IC2") (pin "6") (pinfunction "VDDIO_6") (pintype "power_in"))
      (node (ref "R21") (pin "2") (pinfunction "2_2") (pintype "passive"))
      (node (ref "R22") (pin "2") (pinfunction "2_2") (pintype "passive"))
    )
    (net (code "67") (name "unconnected-(IC2-SDO-Pad5)") (class "Default")
      (node (ref "IC2") (pin "5") (pinfunction "SDO_5") (pintype "input"))
    )
    (net (code "68") (name "unconnected-(U$1-~{INT}-Pad17)") (class "Default")
      (node (ref "U$1") (pin "17") (pinfunction "~{INT}_17") (pintype "output"))
    )
    (net (code "69") (name "unconnected-(U$2A-GPIO_8-PadP8.35)") (class "Default")
      (node (ref "U$2") (pin "P8.35") (pinfunction "GPIO_8_P8.35") (pintype "bidirectional"))
    )
    (net (code "70") (name "unconnected-(U$2A-GPIO_9-PadP8.33)") (class "Default")
      (node (ref "U$2") (pin "P8.33") (pinfunction "GPIO_9_P8.33") (pintype "bidirectional"))
    )
    (net (code "71") (name "unconnected-(U$2A-GPIO_10-PadP8.31)") (class "Default")
      (node (ref "U$2") (pin "P8.31") (pinfunction "GPIO_10_P8.31") (pintype "bidirectional"))
    )
    (net (code "72") (name "unconnected-(U$2A-GPIO_11-PadP8.32)") (class "Default")
      (node (ref "U$2") (pin "P8.32") (pinfunction "GPIO_11_P8.32") (pintype "bidirectional"))
    )
    (net (code "73") (name "unconnected-(U$2A-GPIO_22-PadP8.19)") (class "Default")
      (node (ref "U$2") (pin "P8.19") (pinfunction "GPIO_22_P8.19") (pintype "bidirectional"))
    )
    (net (code "74") (name "unconnected-(U$2A-GPIO_23-PadP8.13)") (class "Default")
      (node (ref "U$2") (pin "P8.13") (pinfunction "GPIO_23_P8.13") (pintype "bidirectional"))
    )
    (net (code "75") (name "unconnected-(U$2A-GPIO_26-PadP8.14)") (class "Default")
      (node (ref "U$2") (pin "P8.14") (pinfunction "GPIO_26_P8.14") (pintype "bidirectional"))
    )
    (net (code "76") (name "unconnected-(U$2A-GPIO_27-PadP8.17)") (class "Default")
      (node (ref "U$2") (pin "P8.17") (pinfunction "GPIO_27_P8.17") (pintype "bidirectional"))
    )
    (net (code "77") (name "unconnected-(U$2A-GPIO_32-PadP8.25)") (class "Default")
      (node (ref "U$2") (pin "P8.25") (pinfunction "GPIO_32_P8.25") (pintype "bidirectional"))
    )
    (net (code "78") (name "unconnected-(U$2A-GPIO_33-PadP8.24)") (class "Default")
      (node (ref "U$2") (pin "P8.24") (pinfunction "GPIO_33_P8.24") (pintype "bidirectional"))
    )
    (net (code "79") (name "unconnected-(U$2A-GPIO_34-PadP8.5)") (class "Default")
      (node (ref "U$2") (pin "P8.5") (pinfunction "GPIO_34_P8.5") (pintype "bidirectional"))
    )
    (net (code "80") (name "unconnected-(U$2A-GPIO_35-PadP8.6)") (class "Default")
      (node (ref "U$2") (pin "P8.6") (pinfunction "GPIO_35_P8.6") (pintype "bidirectional"))
    )
    (net (code "81") (name "unconnected-(U$2A-GPIO_36-PadP8.23)") (class "Default")
      (node (ref "U$2") (pin "P8.23") (pinfunction "GPIO_36_P8.23") (pintype "bidirectional"))
    )
    (net (code "82") (name "unconnected-(U$2A-GPIO_37-PadP8.22)") (class "Default")
      (node (ref "U$2") (pin "P8.22") (pinfunction "GPIO_37_P8.22") (pintype "bidirectional"))
    )
    (net (code "83") (name "unconnected-(U$2A-GPIO_38-PadP8.3)") (class "Default")
      (node (ref "U$2") (pin "P8.3") (pinfunction "GPIO_38_P8.3") (pintype "bidirectional"))
    )
    (net (code "84") (name "unconnected-(U$2A-GPIO_39-PadP8.4)") (class "Default")
      (node (ref "U$2") (pin "P8.4") (pinfunction "GPIO_39_P8.4") (pintype "bidirectional"))
    )
    (net (code "85") (name "unconnected-(U$2A-GPIO_44-PadP8.12)") (class "Default")
      (node (ref "U$2") (pin "P8.12") (pinfunction "GPIO_44_P8.12") (pintype "bidirectional"))
    )
    (net (code "86") (name "unconnected-(U$2A-GPIO_45-PadP8.11)") (class "Default")
      (node (ref "U$2") (pin "P8.11") (pinfunction "GPIO_45_P8.11") (pintype "bidirectional"))
    )
    (net (code "87") (name "unconnected-(U$2A-GPIO_46-PadP8.16)") (class "Default")
      (node (ref "U$2") (pin "P8.16") (pinfunction "GPIO_46_P8.16") (pintype "bidirectional"))
    )
    (net (code "88") (name "unconnected-(U$2A-GPIO_47-PadP8.15)") (class "Default")
      (node (ref "U$2") (pin "P8.15") (pinfunction "GPIO_47_P8.15") (pintype "bidirectional"))
    )
    (net (code "89") (name "unconnected-(U$2A-GPIO_61-PadP8.26)") (class "Default")
      (node (ref "U$2") (pin "P8.26") (pinfunction "GPIO_61_P8.26") (pintype "bidirectional"))
    )
    (net (code "90") (name "unconnected-(U$2A-GPIO_62-PadP8.21)") (class "Default")
      (node (ref "U$2") (pin "P8.21") (pinfunction "GPIO_62_P8.21") (pintype "bidirectional"))
    )
    (net (code "91") (name "unconnected-(U$2A-GPIO_63-PadP8.20)") (class "Default")
      (node (ref "U$2") (pin "P8.20") (pinfunction "GPIO_63_P8.20") (pintype "bidirectional"))
    )
    (net (code "92") (name "unconnected-(U$2A-GPIO_65-PadP8.18)") (class "Default")
      (node (ref "U$2") (pin "P8.18") (pinfunction "GPIO_65_P8.18") (pintype "bidirectional"))
    )
    (net (code "93") (name "unconnected-(U$2A-GPIO_66-PadP8.7)") (class "Default")
      (node (ref "U$2") (pin "P8.7") (pinfunction "GPIO_66_P8.7") (pintype "bidirectional"))
    )
    (net (code "94") (name "unconnected-(U$2A-GPIO_67-PadP8.8)") (class "Default")
      (node (ref "U$2") (pin "P8.8") (pinfunction "GPIO_67_P8.8") (pintype "bidirectional"))
    )
    (net (code "95") (name "unconnected-(U$2A-GPIO_68-PadP8.10)") (class "Default")
      (node (ref "U$2") (pin "P8.10") (pinfunction "GPIO_68_P8.10") (pintype "bidirectional"))
    )
    (net (code "96") (name "unconnected-(U$2A-GPIO_69-PadP8.9)") (class "Default")
      (node (ref "U$2") (pin "P8.9") (pinfunction "GPIO_69_P8.9") (pintype "bidirectional"))
    )
    (net (code "97") (name "unconnected-(U$2A-GPIO_70-PadP8.45)") (class "Default")
      (node (ref "U$2") (pin "P8.45") (pinfunction "GPIO_70_P8.45") (pintype "bidirectional"))
    )
    (net (code "98") (name "unconnected-(U$2A-GPIO_71-PadP8.46)") (class "Default")
      (node (ref "U$2") (pin "P8.46") (pinfunction "GPIO_71_P8.46") (pintype "bidirectional"))
    )
    (net (code "99") (name "unconnected-(U$2A-GPIO_72-PadP8.43)") (class "Default")
      (node (ref "U$2") (pin "P8.43") (pinfunction "GPIO_72_P8.43") (pintype "bidirectional"))
    )
    (net (code "100") (name "unconnected-(U$2A-GPIO_73-PadP8.44)") (class "Default")
      (node (ref "U$2") (pin "P8.44") (pinfunction "GPIO_73_P8.44") (pintype "bidirectional"))
    )
    (net (code "101") (name "unconnected-(U$2A-GPIO_74-PadP8.41)") (class "Default")
      (node (ref "U$2") (pin "P8.41") (pinfunction "GPIO_74_P8.41") (pintype "bidirectional"))
    )
    (net (code "102") (name "unconnected-(U$2A-GPIO_75-PadP8.42)") (class "Default")
      (node (ref "U$2") (pin "P8.42") (pinfunction "GPIO_75_P8.42") (pintype "bidirectional"))
    )
    (net (code "103") (name "unconnected-(U$2A-GPIO_76-PadP8.39)") (class "Default")
      (node (ref "U$2") (pin "P8.39") (pinfunction "GPIO_76_P8.39") (pintype "bidirectional"))
    )
    (net (code "104") (name "unconnected-(U$2A-GPIO_77-PadP8.40)") (class "Default")
      (node (ref "U$2") (pin "P8.40") (pinfunction "GPIO_77_P8.40") (pintype "bidirectional"))
    )
    (net (code "105") (name "unconnected-(U$2A-GPIO_80-PadP8.36)") (class "Default")
      (node (ref "U$2") (pin "P8.36") (pinfunction "GPIO_80_P8.36") (pintype "bidirectional"))
    )
    (net (code "106") (name "unconnected-(U$2A-GPIO_81-PadP8.34)") (class "Default")
      (node (ref "U$2") (pin "P8.34") (pinfunction "GPIO_81_P8.34") (pintype "bidirectional"))
    )
    (net (code "107") (name "unconnected-(U$2A-GPIO_86-PadP8.27)") (class "Default")
      (node (ref "U$2") (pin "P8.27") (pinfunction "GPIO_86_P8.27") (pintype "bidirectional"))
    )
    (net (code "108") (name "unconnected-(U$2A-GPIO_87-PadP8.29)") (class "Default")
      (node (ref "U$2") (pin "P8.29") (pinfunction "GPIO_87_P8.29") (pintype "bidirectional"))
    )
    (net (code "109") (name "unconnected-(U$2A-GPIO_88-PadP8.28)") (class "Default")
      (node (ref "U$2") (pin "P8.28") (pinfunction "GPIO_88_P8.28") (pintype "bidirectional"))
    )
    (net (code "110") (name "unconnected-(U$2A-GPIO_89-PadP8.30)") (class "Default")
      (node (ref "U$2") (pin "P8.30") (pinfunction "GPIO_89_P8.30") (pintype "bidirectional"))
    )
    (net (code "111") (name "unconnected-(U$2B-AIN0-PadP9.39)") (class "Default")
      (node (ref "U$2") (pin "P9.39") (pinfunction "AIN0_P9.39") (pintype "bidirectional"))
    )
    (net (code "112") (name "unconnected-(U$2B-AIN1-PadP9.40)") (class "Default")
      (node (ref "U$2") (pin "P9.40") (pinfunction "AIN1_P9.40") (pintype "bidirectional"))
    )
    (net (code "113") (name "unconnected-(U$2B-AIN2-PadP9.37)") (class "Default")
      (node (ref "U$2") (pin "P9.37") (pinfunction "AIN2_P9.37") (pintype "bidirectional"))
    )
    (net (code "114") (name "unconnected-(U$2B-AIN3-PadP9.38)") (class "Default")
      (node (ref "U$2") (pin "P9.38") (pinfunction "AIN3_P9.38") (pintype "bidirectional"))
    )
    (net (code "115") (name "unconnected-(U$2B-AIN4-PadP9.33)") (class "Default")
      (node (ref "U$2") (pin "P9.33") (pinfunction "AIN4_P9.33") (pintype "bidirectional"))
    )
    (net (code "116") (name "unconnected-(U$2B-AIN5-PadP9.36)") (class "Default")
      (node (ref "U$2") (pin "P9.36") (pinfunction "AIN5_P9.36") (pintype "bidirectional"))
    )
    (net (code "117") (name "unconnected-(U$2B-AIN6-PadP9.35)") (class "Default")
      (node (ref "U$2") (pin "P9.35") (pinfunction "AIN6_P9.35") (pintype "bidirectional"))
    )
    (net (code "118") (name "unconnected-(U$2B-GNDA_ADC-PadP9.34)") (class "Default")
      (node (ref "U$2") (pin "P9.34") (pinfunction "GNDA_ADC_P9.34") (pintype "bidirectional"))
    )
    (net (code "119") (name "unconnected-(U$2B-GPIO_2-PadP9.22)") (class "Default")
      (node (ref "U$2") (pin "P9.22") (pinfunction "GPIO_2_P9.22") (pintype "bidirectional"))
    )
    (net (code "120") (name "unconnected-(U$2B-GPIO_3-PadP9.21)") (class "Default")
      (node (ref "U$2") (pin "P9.21") (pinfunction "GPIO_3_P9.21") (pintype "bidirectional"))
    )
    (net (code "121") (name "unconnected-(U$2B-GPIO_14-PadP9.26)") (class "Default")
      (node (ref "U$2") (pin "P9.26") (pinfunction "GPIO_14_P9.26") (pintype "bidirectional"))
    )
    (net (code "122") (name "unconnected-(U$2B-GPIO_15-PadP9.24)") (class "Default")
      (node (ref "U$2") (pin "P9.24") (pinfunction "GPIO_15_P9.24") (pintype "bidirectional"))
    )
    (net (code "123") (name "unconnected-(U$2B-GPIO_20-PadP9.41)") (class "Default")
      (node (ref "U$2") (pin "P9.41") (pinfunction "GPIO_20_P9.41") (pintype "bidirectional"))
    )
    (net (code "124") (name "unconnected-(U$2B-GPIO_30-PadP9.11)") (class "Default")
      (node (ref "U$2") (pin "P9.11") (pinfunction "GPIO_30_P9.11") (pintype "bidirectional"))
    )
    (net (code "125") (name "unconnected-(U$2B-GPIO_31-PadP9.13)") (class "Default")
      (node (ref "U$2") (pin "P9.13") (pinfunction "GPIO_31_P9.13") (pintype "bidirectional"))
    )
    (net (code "126") (name "unconnected-(U$2B-GPIO_40-PadP9.14)") (class "Default")
      (node (ref "U$2") (pin "P9.14") (pinfunction "GPIO_40_P9.14") (pintype "bidirectional"))
    )
    (net (code "127") (name "unconnected-(U$2B-GPIO_48-PadP9.15)") (class "Default")
      (node (ref "U$2") (pin "P9.15") (pinfunction "GPIO_48_P9.15") (pintype "bidirectional"))
    )
    (net (code "128") (name "unconnected-(U$2B-GPIO_49-PadP9.23)") (class "Default")
      (node (ref "U$2") (pin "P9.23") (pinfunction "GPIO_49_P9.23") (pintype "bidirectional"))
    )
    (net (code "129") (name "unconnected-(U$2B-GPIO_51-PadP9.16)") (class "Default")
      (node (ref "U$2") (pin "P9.16") (pinfunction "GPIO_51_P9.16") (pintype "bidirectional"))
    )
    (net (code "130") (name "unconnected-(U$2B-GPIO_60-PadP9.12)") (class "Default")
      (node (ref "U$2") (pin "P9.12") (pinfunction "GPIO_60_P9.12") (pintype "bidirectional"))
    )
    (net (code "131") (name "unconnected-(U$2B-GPIO_117-PadP9.25)") (class "Default")
      (node (ref "U$2") (pin "P9.25") (pinfunction "GPIO_117_P9.25") (pintype "bidirectional"))
    )
    (net (code "132") (name "unconnected-(U$2B-GPIO_125-PadP9.27)") (class "Default")
      (node (ref "U$2") (pin "P9.27") (pinfunction "GPIO_125_P9.27") (pintype "bidirectional"))
    )
    (net (code "133") (name "unconnected-(U$2B-PWR_BUT-PadP9.9)") (class "Default")
      (node (ref "U$2") (pin "P9.9") (pinfunction "PWR_BUT_P9.9") (pintype "bidirectional"))
    )
    (net (code "134") (name "unconnected-(U$2B-SYS_5V-PadP9.7)") (class "Default")
      (node (ref "U$2") (pin "P9.7") (pinfunction "SYS_5V_P9.7") (pintype "bidirectional"))
    )
    (net (code "135") (name "unconnected-(U$2B-SYS_5V-PadP9.8)") (class "Default")
      (node (ref "U$2") (pin "P9.8") (pinfunction "SYS_5V_P9.8") (pintype "bidirectional"))
    )
    (net (code "136") (name "unconnected-(U$2B-VDD_5V-PadP9.5)") (class "Default")
      (node (ref "U$2") (pin "P9.5") (pinfunction "VDD_5V_P9.5") (pintype "bidirectional"))
    )
    (net (code "137") (name "unconnected-(U$2B-VDD_5V-PadP9.6)") (class "Default")
      (node (ref "U$2") (pin "P9.6") (pinfunction "VDD_5V_P9.6") (pintype "bidirectional"))
    )
    (net (code "138") (name "unconnected-(U$2B-VDD_ADC-PadP9.32)") (class "Default")
      (node (ref "U$2") (pin "P9.32") (pinfunction "VDD_ADC_P9.32") (pintype "bidirectional"))
    )
    (net (code "139") (name "unconnected-(U$3-~{INT}-Pad17)") (class "Default")
      (node (ref "U$3") (pin "17") (pinfunction "~{INT}_17") (pintype "output"))
    )
    (net (code "140") (name "unconnected-(U$5-HOLD_~{THRU}-Pad5)") (class "Default")
      (node (ref "U$5") (pin "5") (pinfunction "HOLD_~{THRU}_5") (pintype "bidirectional"))
    )
    (net (code "141") (name "unconnected-(U$5-SHDN-Pad1)") (class "Default")
      (node (ref "U$5") (pin "1") (pinfunction "SHDN_1") (pintype "bidirectional"))
    )
    (net (code "142") (name "unconnected-(U$6-HOLD_~{THRU}-Pad5)") (class "Default")
      (node (ref "U$6") (pin "5") (pinfunction "HOLD_~{THRU}_5") (pintype "bidirectional"))
    )
    (net (code "143") (name "unconnected-(U$6-SHDN-Pad1)") (class "Default")
      (node (ref "U$6") (pin "1") (pinfunction "SHDN_1") (pintype "bidirectional"))
    )
    (net (code "144") (name "unconnected-(U$7-HOLD_~{THRU}-Pad5)") (class "Default")
      (node (ref "U$7") (pin "5") (pinfunction "HOLD_~{THRU}_5") (pintype "bidirectional"))
    )
    (net (code "145") (name "unconnected-(U$7-SHDN-Pad1)") (class "Default")
      (node (ref "U$7") (pin "1") (pinfunction "SHDN_1") (pintype "bidirectional"))
    )
    (net (code "146") (name "unconnected-(U$8-HOLD_~{THRU}-Pad5)") (class "Default")
      (node (ref "U$8") (pin "5") (pinfunction "HOLD_~{THRU}_5") (pintype "bidirectional"))
    )
    (net (code "147") (name "unconnected-(U$8-SHDN-Pad1)") (class "Default")
      (node (ref "U$8") (pin "1") (pinfunction "SHDN_1") (pintype "bidirectional"))
    )
    (net (code "148") (name "unconnected-(U3-DEN_A{slash}G-Pad13)") (class "Default")
      (node (ref "U3") (pin "13") (pinfunction "DEN_A/G_13") (pintype "bidirectional"))
    )
    (net (code "149") (name "unconnected-(U3-DRDY_M-Pad9)") (class "Default")
      (node (ref "U3") (pin "9") (pinfunction "DRDY_M_9") (pintype "bidirectional"))
    )
    (net (code "150") (name "unconnected-(U3-INT1_A{slash}G-Pad11)") (class "Default")
      (node (ref "U3") (pin "11") (pinfunction "INT1_A/G_11") (pintype "bidirectional"))
    )
    (net (code "151") (name "unconnected-(U3-INT2_A{slash}G-Pad12)") (class "Default")
      (node (ref "U3") (pin "12") (pinfunction "INT2_A/G_12") (pintype "bidirectional"))
    )
    (net (code "152") (name "unconnected-(U3-INT_M-Pad10)") (class "Default")
      (node (ref "U3") (pin "10") (pinfunction "INT_M_10") (pintype "bidirectional"))
    )
    (net (code "153") (name "unconnected-(X2-S1-PadS@1)") (class "Default")
      (node (ref "X2") (pin "S@1") (pinfunction "S1_S@1") (pintype "passive"))
    )
    (net (code "154") (name "unconnected-(X2-S2-PadS@2)") (class "Default")
      (node (ref "X2") (pin "S@2") (pinfunction "S2_S@2") (pintype "passive"))
    )
  )
)
